# Thermistors.net
KiCad netlist of a schematic drawn in Altium Designer
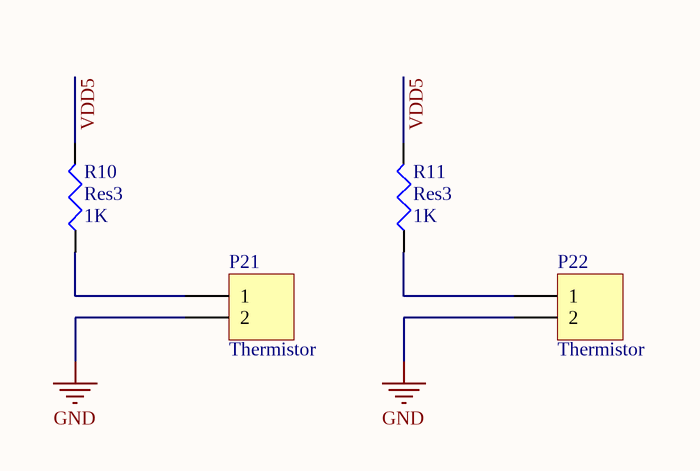
[diagram p0: Thermistors.SchDoc]

(export (version "E")
  (design (tool "Eeschema 10.0.6"))
  (components
    (comp (ref "P21")
      (value "Thermistor")
      (footprint "HDR1X2")
      (description "Header, 2-Pin")
      (fields (field (name "PUBLISHER") "Altium Limited"))
      (libsource (lib "Miscellaneous Connectors") (part "Header 2"))
    )
    (comp (ref "P22")
      (value "Thermistor")
      (footprint "HDR1X2")
      (description "Header, 2-Pin")
      (fields (field (name "PUBLISHER") "Altium Limited"))
      (libsource (lib "Miscellaneous Connectors") (part "Header 2"))
    )
    (comp (ref "R10")
      (value "Res3")
      (footprint "6-0805_L")
      (description "Resistor")
      (fields (field (name "ALTIUM_VALUE") "1K") (field (name "PUBLISHER") "Altium Limited"))
      (libsource (lib "Miscellaneous Devices") (part "Res3"))
    )
    (comp (ref "R11")
      (value "Res3")
      (footprint "6-0805_L")
      (description "Resistor")
      (fields (field (name "ALTIUM_VALUE") "1K") (field (name "PUBLISHER") "Altium Limited"))
      (libsource (lib "Miscellaneous Devices") (part "Res3"))
    )
  )
  (nets
    (net (code "1") (name "/VDD5") (class "Default")
      (node (ref "R10") (pin "2") (pinfunction "2_2") (pintype "passive"))
      (node (ref "R11") (pin "2") (pinfunction "2_2") (pintype "passive"))
    )
    (net (code "2") (name "GND") (class "Default")
      (node (ref "P21") (pin "2") (pinfunction "2_2") (pintype "passive"))
      (node (ref "P22") (pin "2") (pinfunction "2_2") (pintype "passive"))
    )
    (net (code "3") (name "Net-(P21-Pad1)") (class "Default")
      (node (ref "P21") (pin "1") (pinfunction "1_1") (pintype "passive"))
      (node (ref "R10") (pin "1") (pinfunction "1_1") (pintype "passive"))
    )
    (net (code "4") (name "Net-(P22-Pad1)") (class "Default")
      (node (ref "P22") (pin "1") (pinfunction "1_1") (pintype "passive"))
      (node (ref "R11") (pin "1") (pinfunction "1_1") (pintype "passive"))
    )
  )
)
